# Input.net
KiCad netlist of a schematic drawn in Altium Designer
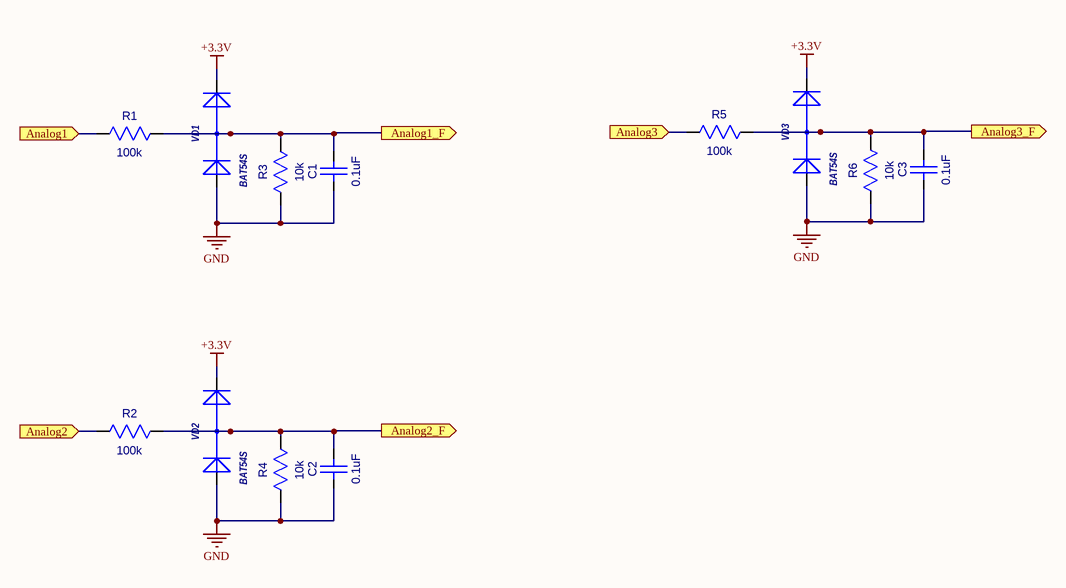
[diagram p0: Input.SchDoc]

(export (version "E")
  (design (tool "Eeschema 10.0.6"))
  (components
    (comp (ref "C1")
      (value "0.1uF")
      (footprint "CC0603-3M")
      (description "CC0603")
      (libsource (lib "gprs_modem") (part "CC0603"))
    )
    (comp (ref "C2")
      (value "0.1uF")
      (footprint "CC0603-3M")
      (description "CC0603")
      (libsource (lib "gprs_modem") (part "CC0603"))
    )
    (comp (ref "C3")
      (value "0.1uF")
      (footprint "CC0603-3M")
      (description "CC0603")
      (libsource (lib "gprs_modem") (part "CC0603"))
    )
    (comp (ref "R1")
      (value "100k")
      (footprint "RC0603-3M")
      (description "RC0603")
      (libsource (lib "gprs_modem") (part "RC0603"))
    )
    (comp (ref "R2")
      (value "100k")
      (footprint "RC0603-3M")
      (description "RC0603")
      (libsource (lib "gprs_modem") (part "RC0603"))
    )
    (comp (ref "R3")
      (value "10k")
      (footprint "RC0603-3M")
      (description "RC0603")
      (libsource (lib "gprs_modem") (part "RC0603"))
    )
    (comp (ref "R4")
      (value "10k")
      (footprint "RC0603-3M")
      (description "RC0603")
      (libsource (lib "gprs_modem") (part "RC0603"))
    )
    (comp (ref "R5")
      (value "100k")
      (footprint "RC0603-3M")
      (description "RC0603")
      (libsource (lib "gprs_modem") (part "RC0603"))
    )
    (comp (ref "R6")
      (value "10k")
      (footprint "RC0603-3M")
      (description "RC0603")
      (libsource (lib "gprs_modem") (part "RC0603"))
    )
    (comp (ref "VD1")
      (value "BAT54S")
      (footprint "SOT-23(GSD)")
      (description "1.0 Ampere General Purpose Rectifier")
      (libsource (lib "gprs_modem") (part "BAT54S"))
    )
    (comp (ref "VD2")
      (value "BAT54S")
      (footprint "SOT-23(GSD)")
      (description "1.0 Ampere General Purpose Rectifier")
      (libsource (lib "gprs_modem") (part "BAT54S"))
    )
    (comp (ref "VD3")
      (value "BAT54S")
      (footprint "SOT-23(GSD)")
      (description "1.0 Ampere General Purpose Rectifier")
      (libsource (lib "gprs_modem") (part "BAT54S"))
    )
  )
  (nets
    (net (code "1") (name "+3.3V") (class "Default")
      (node (ref "VD1") (pin "2") (pinfunction "K_2") (pintype "passive"))
      (node (ref "VD2") (pin "2") (pinfunction "K_2") (pintype "passive"))
      (node (ref "VD3") (pin "2") (pinfunction "K_2") (pintype "passive"))
    )
    (net (code "2") (name "/Analog1") (class "Default")
      (node (ref "R1") (pin "1") (pinfunction "A_1") (pintype "passive"))
    )
    (net (code "3") (name "/Analog1_F") (class "Default")
      (node (ref "C1") (pin "2") (pinfunction "B_2") (pintype "passive"))
      (node (ref "R1") (pin "2") (pinfunction "B_2") (pintype "passive"))
      (node (ref "R3") (pin "2") (pinfunction "B_2") (pintype "passive"))
      (node (ref "VD1") (pin "3") (pinfunction "AK_3") (pintype "passive"))
    )
    (net (code "4") (name "/Analog2") (class "Default")
      (node (ref "R2") (pin "1") (pinfunction "A_1") (pintype "passive"))
    )
    (net (code "5") (name "/Analog2_F") (class "Default")
      (node (ref "C2") (pin "2") (pinfunction "B_2") (pintype "passive"))
      (node (ref "R2") (pin "2") (pinfunction "B_2") (pintype "passive"))
      (node (ref "R4") (pin "2") (pinfunction "B_2") (pintype "passive"))
      (node (ref "VD2") (pin "3") (pinfunction "AK_3") (pintype "passive"))
    )
    (net (code "6") (name "/Analog3") (class "Default")
      (node (ref "R5") (pin "1") (pinfunction "A_1") (pintype "passive"))
    )
    (net (code "7") (name "/Analog3_F") (class "Default")
      (node (ref "C3") (pin "2") (pinfunction "B_2") (pintype "passive"))
      (node (ref "R5") (pin "2") (pinfunction "B_2") (pintype "passive"))
      (node (ref "R6") (pin "2") (pinfunction "B_2") (pintype "passive"))
      (node (ref "VD3") (pin "3") (pinfunction "AK_3") (pintype "passive"))
    )
    (net (code "8") (name "GND") (class "Default")
      (node (ref "C1") (pin "1") (pinfunction "A_1") (pintype "passive"))
      (node (ref "C2") (pin "1") (pinfunction "A_1") (pintype "passive"))
      (node (ref "C3") (pin "1") (pinfunction "A_1") (pintype "passive"))
      (node (ref "R3") (pin "1") (pinfunction "A_1") (pintype "passive"))
      (node (ref "R4") (pin "1") (pinfunction "A_1") (pintype "passive"))
      (node (ref "R6") (pin "1") (pinfunction "A_1") (pintype "passive"))
      (node (ref "VD1") (pin "1") (pinfunction "A_1") (pintype "passive"))
      (node (ref "VD2") (pin "1") (pinfunction "A_1") (pintype "passive"))
      (node (ref "VD3") (pin "1") (pinfunction "A_1") (pintype "passive"))
    )
  )
)
